# PLD_Gyroscopes.net
KiCad netlist of a schematic drawn in Altium Designer
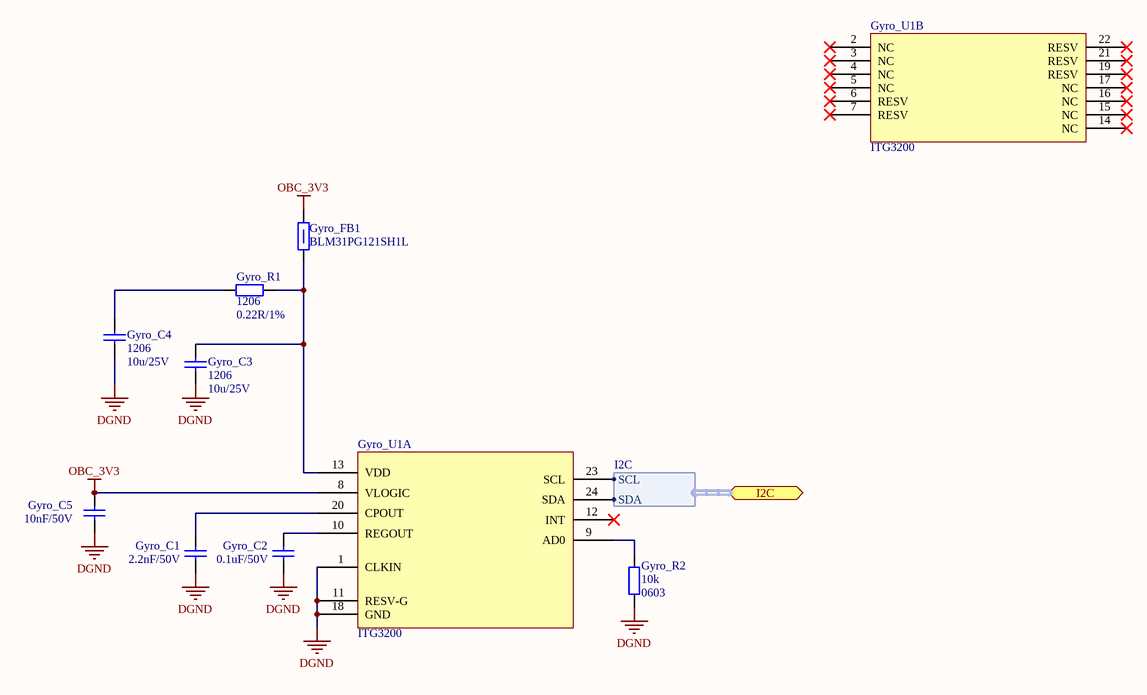
[diagram p0: PLD_Gyroscopes.SchDoc]

(export (version "E")
  (design (tool "Eeschema 10.0.6"))
  (components
    (comp (ref "Gyro_C1")
      (value "2.2nF/50V")
      (footprint "SMD_Capacitor_0603")
      (description "Ceramic Cap Kemet COTS 100n/50V X7R 0603")
      (fields
        (field (name "MANUFACTURER") "Kemet")
        (field (name "MANUFACTURERPARTNUMBER") "C0603T104K5RALTU")
      )
      (libsource (lib "capacitors") (part "Cer_C0603T104K5RALTU"))
    )
    (comp (ref "Gyro_C2")
      (value "0.1uF/50V")
      (footprint "SMD_Capacitor_0603")
      (description "Ceramic Cap Kemet COTS 100n/50V X7R 0603")
      (fields
        (field (name "MANUFACTURER") "Kemet")
        (field (name "MANUFACTURERPARTNUMBER") "C0603T104K5RALTU")
      )
      (libsource (lib "capacitors") (part "Cer_C0603T104K5RALTU"))
    )
    (comp (ref "Gyro_C3")
      (value "10u/25V")
      (footprint "SMD_Capacitor_1206")
      (description "Ceramic Cap Kemet COTS 1u/25V X7R 1206")
      (fields
        (field (name "MANUFACTURERPARTNUMBER") "C1206T105K3RALTU")
        (field (name "MANUFACTURER") "Kemet")
        (field (name "PACKAGE") "1206")
      )
      (libsource (lib "capacitors") (part "Cer_C1206T105K3RALTU"))
    )
    (comp (ref "Gyro_C4")
      (value "10u/25V")
      (footprint "SMD_Capacitor_1206")
      (description "Ceramic Cap Kemet COTS 1u/25V X7R 1206")
      (fields
        (field (name "MANUFACTURERPARTNUMBER") "C1206T105K3RALTU")
        (field (name "MANUFACTURER") "Kemet")
        (field (name "PACKAGE") "1206")
      )
      (libsource (lib "capacitors") (part "Cer_C1206T105K3RALTU"))
    )
    (comp (ref "Gyro_C5")
      (value "10nF/50V")
      (footprint "SMD_Capacitor_0603")
      (description "Ceramic Cap Kemet COTS 100n/50V X7R 0603")
      (fields
        (field (name "MANUFACTURER") "Kemet")
        (field (name "MANUFACTURERPARTNUMBER") "C0603T104K5RALTU")
      )
      (libsource (lib "capacitors") (part "Cer_C0603T104K5RALTU"))
    )
    (comp (ref "Gyro_FB1")
      (value "120R/100MHz")
      (footprint "SMD_FerriteBead_1206")
      (description "Ferrite bead, 1206, 0.02HM, 3.5A.")
      (fields (field (name "MANUFACTURER") "Murata") (field (name "MANUFACTURERPARTNUMBER") "BLM31PG121SH1L"))
      (libsource (lib "inductors") (part "BLM31PG121SH1L"))
    )
    (comp (ref "Gyro_R1")
      (value "0.22R/1%")
      (footprint "SMD_Resistor_1206")
      (description "Panasonic Resistor 0.22R 1% 1206 330mW")
      (fields
        (field (name "MANUFACTURER") "Panasonic")
        (field (name "MANUFACTURERPARTNUMBER") "ERJ-8BQFR22V")
        (field (name "PACKAGE") "1206")
      )
      (libsource (lib "resistors") (part "ERJ-8BQFR22V"))
    )
    (comp (ref "Gyro_R2")
      (value "10k")
      (footprint "SMD_Resistor_0603")
      (fields (field (name "PACKAGE") "0603"))
      (libsource (lib "resistors") (part "Res"))
    )
    (comp (ref "Gyro_U1") (value "ITG3200") (footprint "QFN24_4x4") (libsource (lib "mems") (part "ITG3200")))
  )
  (nets
    (net (code "2") (name "/SCL") (class "Default")
      (node (ref "Gyro_U1") (pin "23") (pinfunction "SCL_23") (pintype "passive"))
    )
    (net (code "3") (name "/SDA") (class "Default")
      (node (ref "Gyro_U1") (pin "24") (pinfunction "SDA_24") (pintype "passive"))
    )
    (net (code "5") (name "DGND") (class "Default")
      (node (ref "Gyro_C1") (pin "2") (pinfunction "2_2") (pintype "passive"))
      (node (ref "Gyro_C2") (pin "2") (pinfunction "2_2") (pintype "passive"))
      (node (ref "Gyro_C3") (pin "2") (pinfunction "2_2") (pintype "passive"))
      (node (ref "Gyro_C4") (pin "2") (pinfunction "2_2") (pintype "passive"))
      (node (ref "Gyro_C5") (pin "2") (pinfunction "2_2") (pintype "passive"))
      (node (ref "Gyro_R2") (pin "2") (pinfunction "2_2") (pintype "passive"))
      (node (ref "Gyro_U1") (pin "1") (pinfunction "CLKIN_1") (pintype "passive"))
      (node (ref "Gyro_U1") (pin "11") (pinfunction "RESV-G_11") (pintype "passive"))
      (node (ref "Gyro_U1") (pin "18") (pinfunction "GND_18") (pintype "passive"))
    )
    (net (code "6") (name "Net-(Gyro_C4-Pad1)") (class "Default")
      (node (ref "Gyro_C4") (pin "1") (pinfunction "1_1") (pintype "passive"))
      (node (ref "Gyro_R1") (pin "1") (pinfunction "1_1") (pintype "passive"))
    )
    (net (code "7") (name "Net-(Gyro_U1A-AD0)") (class "Default")
      (node (ref "Gyro_R2") (pin "1") (pinfunction "1_1") (pintype "passive"))
      (node (ref "Gyro_U1") (pin "9") (pinfunction "AD0_9") (pintype "passive"))
    )
    (net (code "8") (name "Net-(Gyro_U1A-CPOUT)") (class "Default")
      (node (ref "Gyro_C1") (pin "1") (pinfunction "1_1") (pintype "passive"))
      (node (ref "Gyro_U1") (pin "20") (pinfunction "CPOUT_20") (pintype "passive"))
    )
    (net (code "9") (name "Net-(Gyro_U1A-REGOUT)") (class "Default")
      (node (ref "Gyro_C2") (pin "1") (pinfunction "1_1") (pintype "passive"))
      (node (ref "Gyro_U1") (pin "10") (pinfunction "REGOUT_10") (pintype "passive"))
    )
    (net (code "10") (name "Net-(Gyro_U1A-VDD)") (class "Default")
      (node (ref "Gyro_C3") (pin "1") (pinfunction "1_1") (pintype "passive"))
      (node (ref "Gyro_FB1") (pin "2") (pinfunction "2_2") (pintype "passive"))
      (node (ref "Gyro_R1") (pin "2") (pinfunction "2_2") (pintype "passive"))
      (node (ref "Gyro_U1") (pin "13") (pinfunction "VDD_13") (pintype "passive"))
    )
    (net (code "11") (name "OBC_3V3") (class "Default")
      (node (ref "Gyro_C5") (pin "1") (pinfunction "1_1") (pintype "passive"))
      (node (ref "Gyro_FB1") (pin "1") (pinfunction "1_1") (pintype "passive"))
      (node (ref "Gyro_U1") (pin "8") (pinfunction "VLOGIC_8") (pintype "passive"))
    )
    (net (code "12") (name "unconnected-(Gyro_U1A-INT-Pad12)") (class "Default")
      (node (ref "Gyro_U1") (pin "12") (pinfunction "INT_12") (pintype "passive+no_connect"))
    )
    (net (code "13") (name "unconnected-(Gyro_U1B-NC-Pad2)") (class "Default")
      (node (ref "Gyro_U1") (pin "2") (pinfunction "NC_2") (pintype "passive+no_connect"))
    )
    (net (code "14") (name "unconnected-(Gyro_U1B-NC-Pad3)") (class "Default")
      (node (ref "Gyro_U1") (pin "3") (pinfunction "NC_3") (pintype "passive+no_connect"))
    )
    (net (code "15") (name "unconnected-(Gyro_U1B-NC-Pad4)") (class "Default")
      (node (ref "Gyro_U1") (pin "4") (pinfunction "NC_4") (pintype "passive+no_connect"))
    )
    (net (code "16") (name "unconnected-(Gyro_U1B-NC-Pad5)") (class "Default")
      (node (ref "Gyro_U1") (pin "5") (pinfunction "NC_5") (pintype "passive+no_connect"))
    )
    (net (code "17") (name "unconnected-(Gyro_U1B-NC-Pad14)") (class "Default")
      (node (ref "Gyro_U1") (pin "14") (pinfunction "NC_14") (pintype "passive+no_connect"))
    )
    (net (code "18") (name "unconnected-(Gyro_U1B-NC-Pad15)") (class "Default")
      (node (ref "Gyro_U1") (pin "15") (pinfunction "NC_15") (pintype "passive+no_connect"))
    )
    (net (code "19") (name "unconnected-(Gyro_U1B-NC-Pad16)") (class "Default")
      (node (ref "Gyro_U1") (pin "16") (pinfunction "NC_16") (pintype "passive+no_connect"))
    )
    (net (code "20") (name "unconnected-(Gyro_U1B-NC-Pad17)") (class "Default")
      (node (ref "Gyro_U1") (pin "17") (pinfunction "NC_17") (pintype "passive+no_connect"))
    )
    (net (code "21") (name "unconnected-(Gyro_U1B-RESV-Pad6)") (class "Default")
      (node (ref "Gyro_U1") (pin "6") (pinfunction "RESV_6") (pintype "passive+no_connect"))
    )
    (net (code "22") (name "unconnected-(Gyro_U1B-RESV-Pad7)") (class "Default")
      (node (ref "Gyro_U1") (pin "7") (pinfunction "RESV_7") (pintype "passive+no_connect"))
    )
    (net (code "23") (name "unconnected-(Gyro_U1B-RESV-Pad19)") (class "Default")
      (node (ref "Gyro_U1") (pin "19") (pinfunction "RESV_19") (pintype "passive+no_connect"))
    )
    (net (code "24") (name "unconnected-(Gyro_U1B-RESV-Pad21)") (class "Default")
      (node (ref "Gyro_U1") (pin "21") (pinfunction "RESV_21") (pintype "passive+no_connect"))
    )
    (net (code "25") (name "unconnected-(Gyro_U1B-RESV-Pad22)") (class "Default")
      (node (ref "Gyro_U1") (pin "22") (pinfunction "RESV_22") (pintype "passive+no_connect"))
    )
  )
)
